# accel-sd-gyro.net
KiCad netlist of a schematic drawn in EAGLE
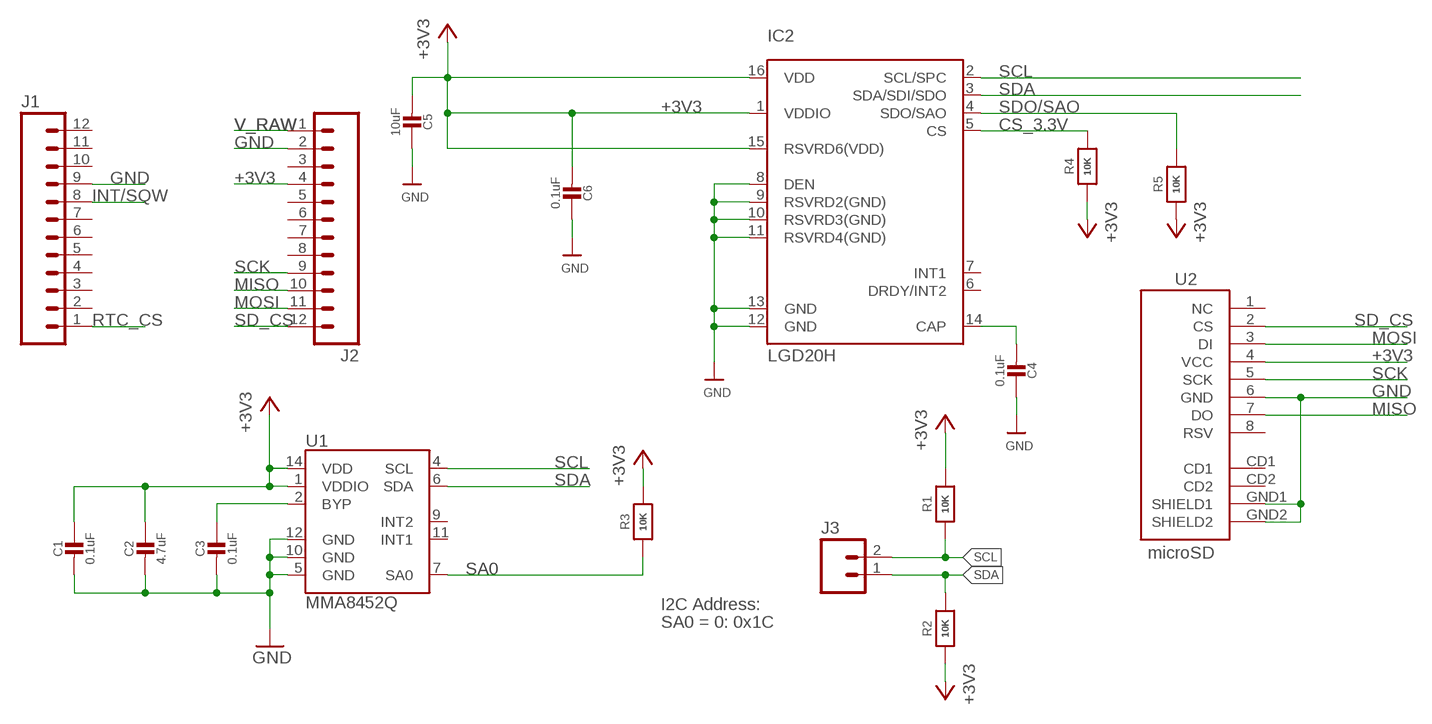
[diagram p0: schematic, sheet 1]

(export (version "E")
  (design (tool "Eeschema 10.0.6"))
  (components
    (comp (ref "C1")
      (value "0.1uF")
      (footprint "eagle-import:0805-NO")
      (libsource (lib "eagle-import") (part "CAP_CERAMIC0805-NOOUTLINE"))
    )
    (comp (ref "C2")
      (value "4.7uF")
      (footprint "eagle-import:0805-NO")
      (libsource (lib "eagle-import") (part "CAP_CERAMIC0805-NOOUTLINE"))
    )
    (comp (ref "C3")
      (value "0.1uF")
      (footprint "eagle-import:0805-NO")
      (libsource (lib "eagle-import") (part "CAP_CERAMIC0805-NOOUTLINE"))
    )
    (comp (ref "C4")
      (value "0.1uF")
      (footprint "eagle-import:0805-NO")
      (libsource (lib "eagle-import") (part "CAP_CERAMIC0805-NOOUTLINE"))
    )
    (comp (ref "C5")
      (value "10uF")
      (footprint "eagle-import:0805-NO")
      (libsource (lib "eagle-import") (part "CAP_CERAMIC0805-NOOUTLINE"))
    )
    (comp (ref "C6")
      (value "0.1uF")
      (footprint "eagle-import:0805-NO")
      (libsource (lib "eagle-import") (part "CAP_CERAMIC0805-NOOUTLINE"))
    )
    (comp (ref "IC2")
      (value "LGD20H")
      (footprint "eagle-import:L3GD20H_LGA16L")
      (libsource (lib "eagle-import") (part "GYRO_L3GD20H"))
    )
    (comp (ref "J1")
      (value "M12PTH")
      (footprint "eagle-import:1X12")
      (libsource (lib "eagle-import") (part "M12PTH"))
    )
    (comp (ref "J2")
      (value "M12PTH")
      (footprint "eagle-import:1X12")
      (libsource (lib "eagle-import") (part "M12PTH"))
    )
    (comp (ref "J3")
      (value "M02LOCK")
      (footprint "eagle-import:1X02_LOCK")
      (libsource (lib "eagle-import") (part "M02LOCK"))
    )
    (comp (ref "R1")
      (value "10K")
      (footprint "eagle-import:0805-NO")
      (libsource (lib "eagle-import") (part "RESISTOR0805_NOOUTLINE"))
    )
    (comp (ref "R2")
      (value "10K")
      (footprint "eagle-import:0805-NO")
      (libsource (lib "eagle-import") (part "RESISTOR0805_NOOUTLINE"))
    )
    (comp (ref "R3")
      (value "10K")
      (footprint "eagle-import:_0805MP")
      (libsource (lib "eagle-import") (part "RESISTOR_0805MP"))
    )
    (comp (ref "R4")
      (value "10K")
      (footprint "eagle-import:0805-NO")
      (libsource (lib "eagle-import") (part "RESISTOR0805_NOOUTLINE"))
    )
    (comp (ref "R5")
      (value "10K")
      (footprint "eagle-import:0805-NO")
      (libsource (lib "eagle-import") (part "RESISTOR0805_NOOUTLINE"))
    )
    (comp (ref "U1")
      (value "MMA8452Q")
      (footprint "eagle-import:QFN-16_0.5MM")
      (libsource (lib "eagle-import") (part "MMA8452Q"))
    )
    (comp (ref "U2")
      (value "microSD")
      (footprint "eagle-import:MICRO-SD-SOCKET-PP")
      (libsource (lib "eagle-import") (part "USD-SOCKETSMD"))
    )
  )
  (nets
    (net (code "1") (name "+3V3") (class "Default")
      (node (ref "C1") (pin "1") (pinfunction "1_1") (pintype "passive"))
      (node (ref "C2") (pin "1") (pinfunction "1_1") (pintype "passive"))
      (node (ref "C5") (pin "2") (pinfunction "2_2") (pintype "passive"))
      (node (ref "C6") (pin "2") (pinfunction "2_2") (pintype "passive"))
      (node (ref "IC2") (pin "1") (pinfunction "VDDIO_1") (pintype "power_in"))
      (node (ref "IC2") (pin "15") (pinfunction "RSVRD6(VDD)_15") (pintype "bidirectional"))
      (node (ref "IC2") (pin "16") (pinfunction "VDD_16") (pintype "bidirectional"))
      (node (ref "J2") (pin "4") (pinfunction "4_4") (pintype "passive"))
      (node (ref "R1") (pin "2") (pinfunction "2_2") (pintype "passive"))
      (node (ref "R2") (pin "1") (pinfunction "1_1") (pintype "passive"))
      (node (ref "R3") (pin "2") (pinfunction "2_2") (pintype "passive"))
      (node (ref "R4") (pin "1") (pinfunction "1_1") (pintype "passive"))
      (node (ref "R5") (pin "1") (pinfunction "1_1") (pintype "passive"))
      (node (ref "U1") (pin "1") (pinfunction "VDDIO_1") (pintype "bidirectional"))
      (node (ref "U1") (pin "14") (pinfunction "VDD_14") (pintype "bidirectional"))
      (node (ref "U2") (pin "4") (pinfunction "VCC_4") (pintype "bidirectional"))
    )
    (net (code "2") (name "/CS_3.3V") (class "Default")
      (node (ref "IC2") (pin "5") (pinfunction "CS_5") (pintype "bidirectional"))
      (node (ref "R4") (pin "2") (pinfunction "2_2") (pintype "passive"))
    )
    (net (code "3") (name "/INT{slash}SQW") (class "Default")
      (node (ref "J1") (pin "8") (pinfunction "8_8") (pintype "passive"))
    )
    (net (code "4") (name "/MISO") (class "Default")
      (node (ref "J2") (pin "10") (pinfunction "10_10") (pintype "passive"))
      (node (ref "U2") (pin "7") (pinfunction "DO_7") (pintype "bidirectional"))
    )
    (net (code "5") (name "/MOSI") (class "Default")
      (node (ref "J2") (pin "11") (pinfunction "11_11") (pintype "passive"))
      (node (ref "U2") (pin "3") (pinfunction "DI_3") (pintype "bidirectional"))
    )
    (net (code "6") (name "/RTC_CS") (class "Default")
      (node (ref "J1") (pin "1") (pinfunction "1_1") (pintype "passive"))
    )
    (net (code "7") (name "/SA0") (class "Default")
      (node (ref "R3") (pin "1") (pinfunction "1_1") (pintype "passive"))
      (node (ref "U1") (pin "7") (pinfunction "SA0_7") (pintype "bidirectional"))
    )
    (net (code "8") (name "/SCK") (class "Default")
      (node (ref "J2") (pin "9") (pinfunction "9_9") (pintype "passive"))
      (node (ref "U2") (pin "5") (pinfunction "SCK_5") (pintype "bidirectional"))
    )
    (net (code "9") (name "/SDO{slash}SAO") (class "Default")
      (node (ref "IC2") (pin "4") (pinfunction "SDO/SAO_4") (pintype "bidirectional"))
      (node (ref "R5") (pin "2") (pinfunction "2_2") (pintype "passive"))
    )
    (net (code "10") (name "/SD_CS") (class "Default")
      (node (ref "J2") (pin "12") (pinfunction "12_12") (pintype "passive"))
      (node (ref "U2") (pin "2") (pinfunction "CS_2") (pintype "bidirectional"))
    )
    (net (code "11") (name "/V_RAW") (class "Default")
      (node (ref "J2") (pin "1") (pinfunction "1_1") (pintype "passive"))
    )
    (net (code "12") (name "GND") (class "Default")
      (node (ref "C1") (pin "2") (pinfunction "2_2") (pintype "passive"))
      (node (ref "C2") (pin "2") (pinfunction "2_2") (pintype "passive"))
      (node (ref "C3") (pin "2") (pinfunction "2_2") (pintype "passive"))
      (node (ref "C4") (pin "1") (pinfunction "1_1") (pintype "passive"))
      (node (ref "C5") (pin "1") (pinfunction "1_1") (pintype "passive"))
      (node (ref "C6") (pin "1") (pinfunction "1_1") (pintype "passive"))
      (node (ref "IC2") (pin "10") (pinfunction "RSVRD3(GND)_10") (pintype "bidirectional"))
      (node (ref "IC2") (pin "11") (pinfunction "RSVRD4(GND)_11") (pintype "bidirectional"))
      (node (ref "IC2") (pin "12") (pinfunction "GND_12") (pintype "bidirectional"))
      (node (ref "IC2") (pin "13") (pinfunction "GND_13") (pintype "bidirectional"))
      (node (ref "IC2") (pin "8") (pinfunction "DEN_8") (pintype "bidirectional"))
      (node (ref "IC2") (pin "9") (pinfunction "RSVRD2(GND)_9") (pintype "bidirectional"))
      (node (ref "J1") (pin "9") (pinfunction "9_9") (pintype "passive"))
      (node (ref "J2") (pin "2") (pinfunction "2_2") (pintype "passive"))
      (node (ref "U1") (pin "10") (pinfunction "GND_10") (pintype "bidirectional"))
      (node (ref "U1") (pin "12") (pinfunction "GND_12") (pintype "bidirectional"))
      (node (ref "U1") (pin "5") (pinfunction "GND_5") (pintype "bidirectional"))
      (node (ref "U2") (pin "6") (pinfunction "GND_6") (pintype "bidirectional"))
      (node (ref "U2") (pin "GND1") (pinfunction "SHIELD1_GND1") (pintype "bidirectional"))
      (node (ref "U2") (pin "GND2") (pinfunction "SHIELD2_GND2") (pintype "bidirectional"))
    )
    (net (code "13") (name "Net-(IC2-CAP)") (class "Default")
      (node (ref "C4") (pin "2") (pinfunction "2_2") (pintype "passive"))
      (node (ref "IC2") (pin "14") (pinfunction "CAP_14") (pintype "bidirectional"))
    )
    (net (code "14") (name "Net-(U1-BYP)") (class "Default")
      (node (ref "C3") (pin "1") (pinfunction "1_1") (pintype "passive"))
      (node (ref "U1") (pin "2") (pinfunction "BYP_2") (pintype "bidirectional"))
    )
    (net (code "15") (name "SCL") (class "Default")
      (node (ref "IC2") (pin "2") (pinfunction "SCL/SPC_2") (pintype "bidirectional"))
      (node (ref "J3") (pin "2") (pinfunction "2_2") (pintype "passive"))
      (node (ref "R1") (pin "1") (pinfunction "1_1") (pintype "passive"))
      (node (ref "U1") (pin "4") (pinfunction "SCL_4") (pintype "bidirectional"))
    )
    (net (code "16") (name "SDA") (class "Default")
      (node (ref "IC2") (pin "3") (pinfunction "SDA/SDI/SDO_3") (pintype "bidirectional"))
      (node (ref "J3") (pin "1") (pinfunction "1_1") (pintype "passive"))
      (node (ref "R2") (pin "2") (pinfunction "2_2") (pintype "passive"))
      (node (ref "U1") (pin "6") (pinfunction "SDA_6") (pintype "bidirectional"))
    )
    (net (code "17") (name "unconnected-(IC2-DRDY{slash}INT2-Pad6)") (class "Default")
      (node (ref "IC2") (pin "6") (pinfunction "DRDY/INT2_6") (pintype "bidirectional"))
    )
    (net (code "18") (name "unconnected-(IC2-INT1-Pad7)") (class "Default")
      (node (ref "IC2") (pin "7") (pinfunction "INT1_7") (pintype "bidirectional"))
    )
    (net (code "19") (name "unconnected-(J1-Pad2)") (class "Default")
      (node (ref "J1") (pin "2") (pinfunction "2_2") (pintype "passive"))
    )
    (net (code "20") (name "unconnected-(J1-Pad3)") (class "Default")
      (node (ref "J1") (pin "3") (pinfunction "3_3") (pintype "passive"))
    )
    (net (code "21") (name "unconnected-(J1-Pad4)") (class "Default")
      (node (ref "J1") (pin "4") (pinfunction "4_4") (pintype "passive"))
    )
    (net (code "22") (name "unconnected-(J1-Pad5)") (class "Default")
      (node (ref "J1") (pin "5") (pinfunction "5_5") (pintype "passive"))
    )
    (net (code "23") (name "unconnected-(J1-Pad6)") (class "Default")
      (node (ref "J1") (pin "6") (pinfunction "6_6") (pintype "passive"))
    )
    (net (code "24") (name "unconnected-(J1-Pad7)") (class "Default")
      (node (ref "J1") (pin "7") (pinfunction "7_7") (pintype "passive"))
    )
    (net (code "25") (name "unconnected-(J1-Pad10)") (class "Default")
      (node (ref "J1") (pin "10") (pinfunction "10_10") (pintype "passive"))
    )
    (net (code "26") (name "unconnected-(J1-Pad11)") (class "Default")
      (node (ref "J1") (pin "11") (pinfunction "11_11") (pintype "passive"))
    )
    (net (code "27") (name "unconnected-(J1-Pad12)") (class "Default")
      (node (ref "J1") (pin "12") (pinfunction "12_12") (pintype "passive"))
    )
    (net (code "28") (name "unconnected-(J2-Pad3)") (class "Default")
      (node (ref "J2") (pin "3") (pinfunction "3_3") (pintype "passive"))
    )
    (net (code "29") (name "unconnected-(J2-Pad5)") (class "Default")
      (node (ref "J2") (pin "5") (pinfunction "5_5") (pintype "passive"))
    )
    (net (code "30") (name "unconnected-(J2-Pad6)") (class "Default")
      (node (ref "J2") (pin "6") (pinfunction "6_6") (pintype "passive"))
    )
    (net (code "31") (name "unconnected-(J2-Pad7)") (class "Default")
      (node (ref "J2") (pin "7") (pinfunction "7_7") (pintype "passive"))
    )
    (net (code "32") (name "unconnected-(J2-Pad8)") (class "Default")
      (node (ref "J2") (pin "8") (pinfunction "8_8") (pintype "passive"))
    )
    (net (code "33") (name "unconnected-(U1-INT1-Pad11)") (class "Default")
      (node (ref "U1") (pin "11") (pinfunction "INT1_11") (pintype "bidirectional"))
    )
    (net (code "34") (name "unconnected-(U1-INT2-Pad9)") (class "Default")
      (node (ref "U1") (pin "9") (pinfunction "INT2_9") (pintype "bidirectional"))
    )
    (net (code "35") (name "unconnected-(U2-NC-Pad1)") (class "Default")
      (node (ref "U2") (pin "1") (pinfunction "NC_1") (pintype "bidirectional"))
    )
    (net (code "36") (name "unconnected-(U2-PadCD1)") (class "Default")
      (node (ref "U2") (pin "CD1") (pinfunction "CD1_CD1") (pintype "bidirectional"))
    )
    (net (code "37") (name "unconnected-(U2-PadCD2)") (class "Default")
      (node (ref "U2") (pin "CD2") (pinfunction "CD2_CD2") (pintype "bidirectional"))
    )
    (net (code "38") (name "unconnected-(U2-RSV-Pad8)") (class "Default")
      (node (ref "U2") (pin "8") (pinfunction "RSV_8") (pintype "bidirectional"))
    )
  )
)
